# 801_USBHub-Framework.net
KiCad netlist of a schematic drawn in Altium Designer
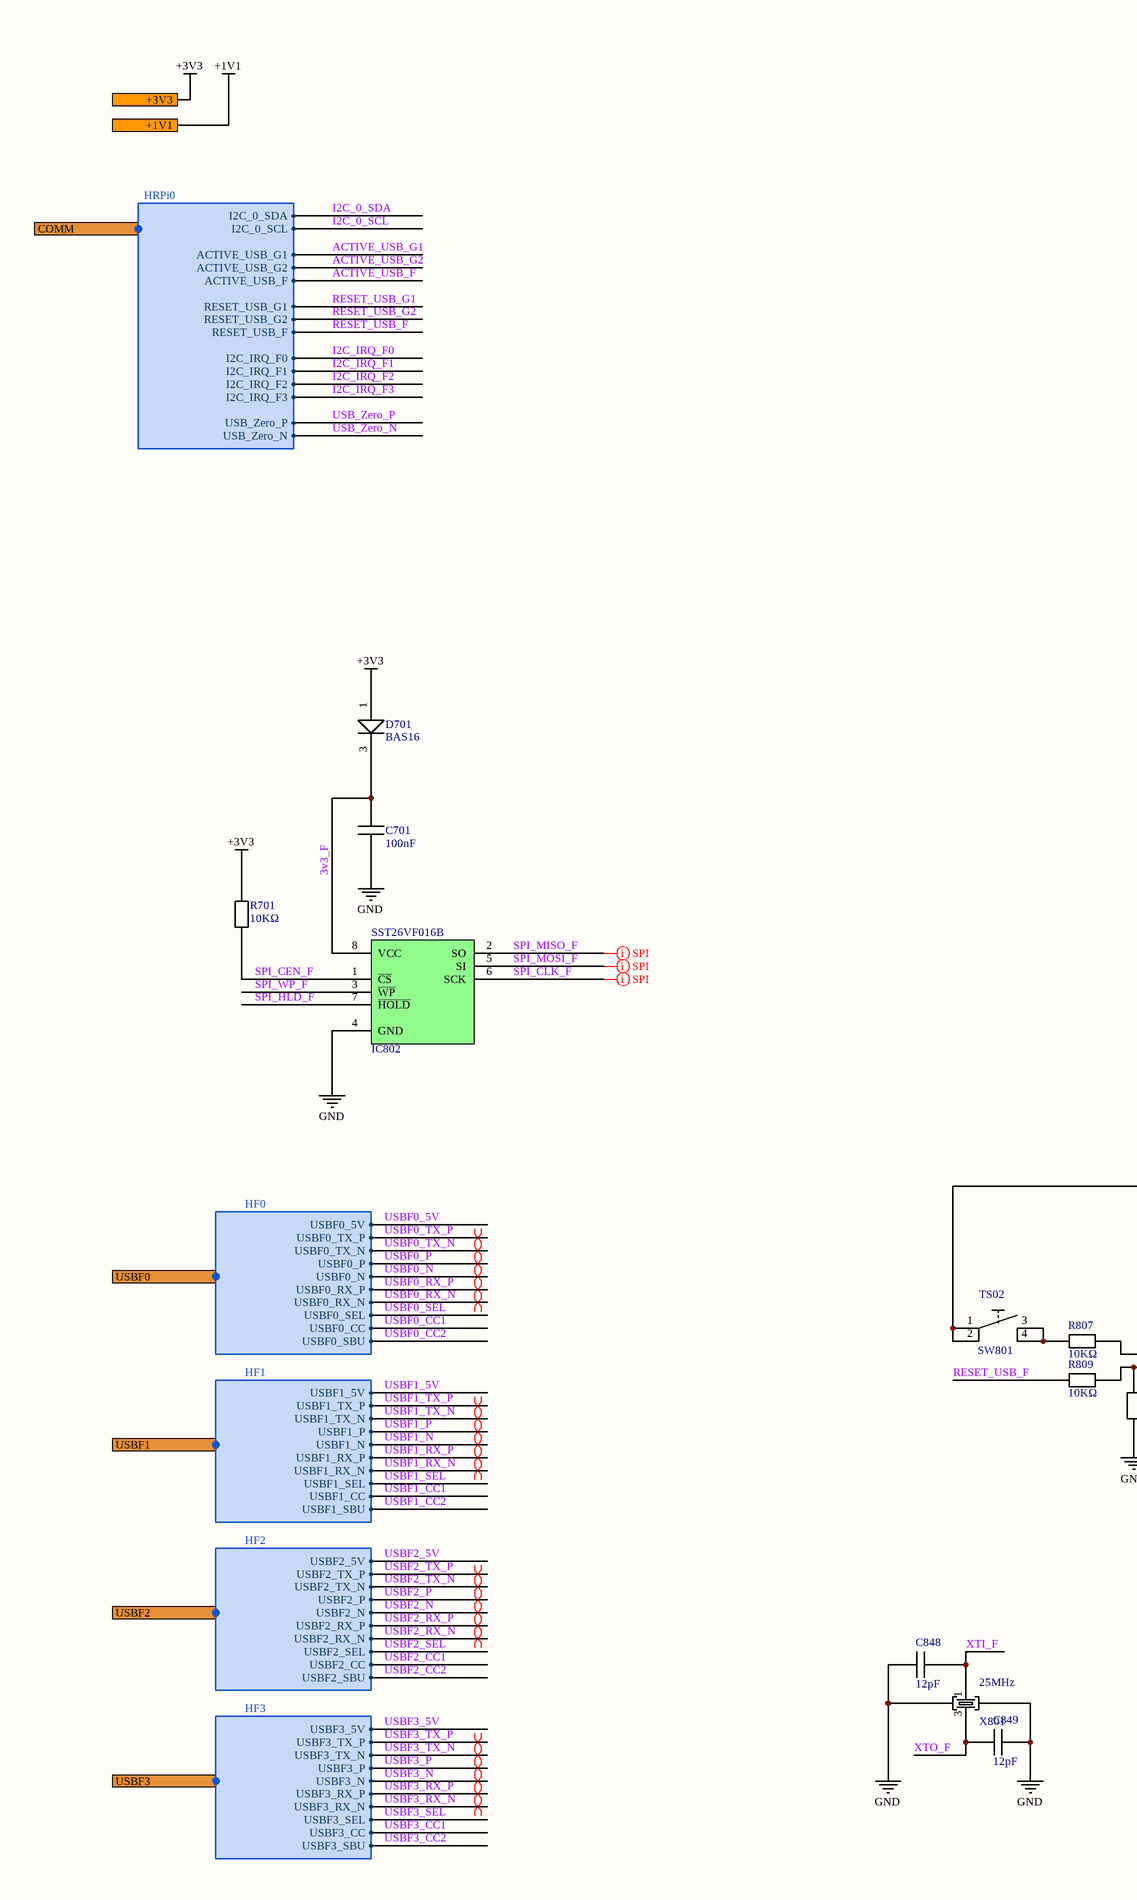
[diagram p0: 801_USBHub-Framework.SchDoc, left]
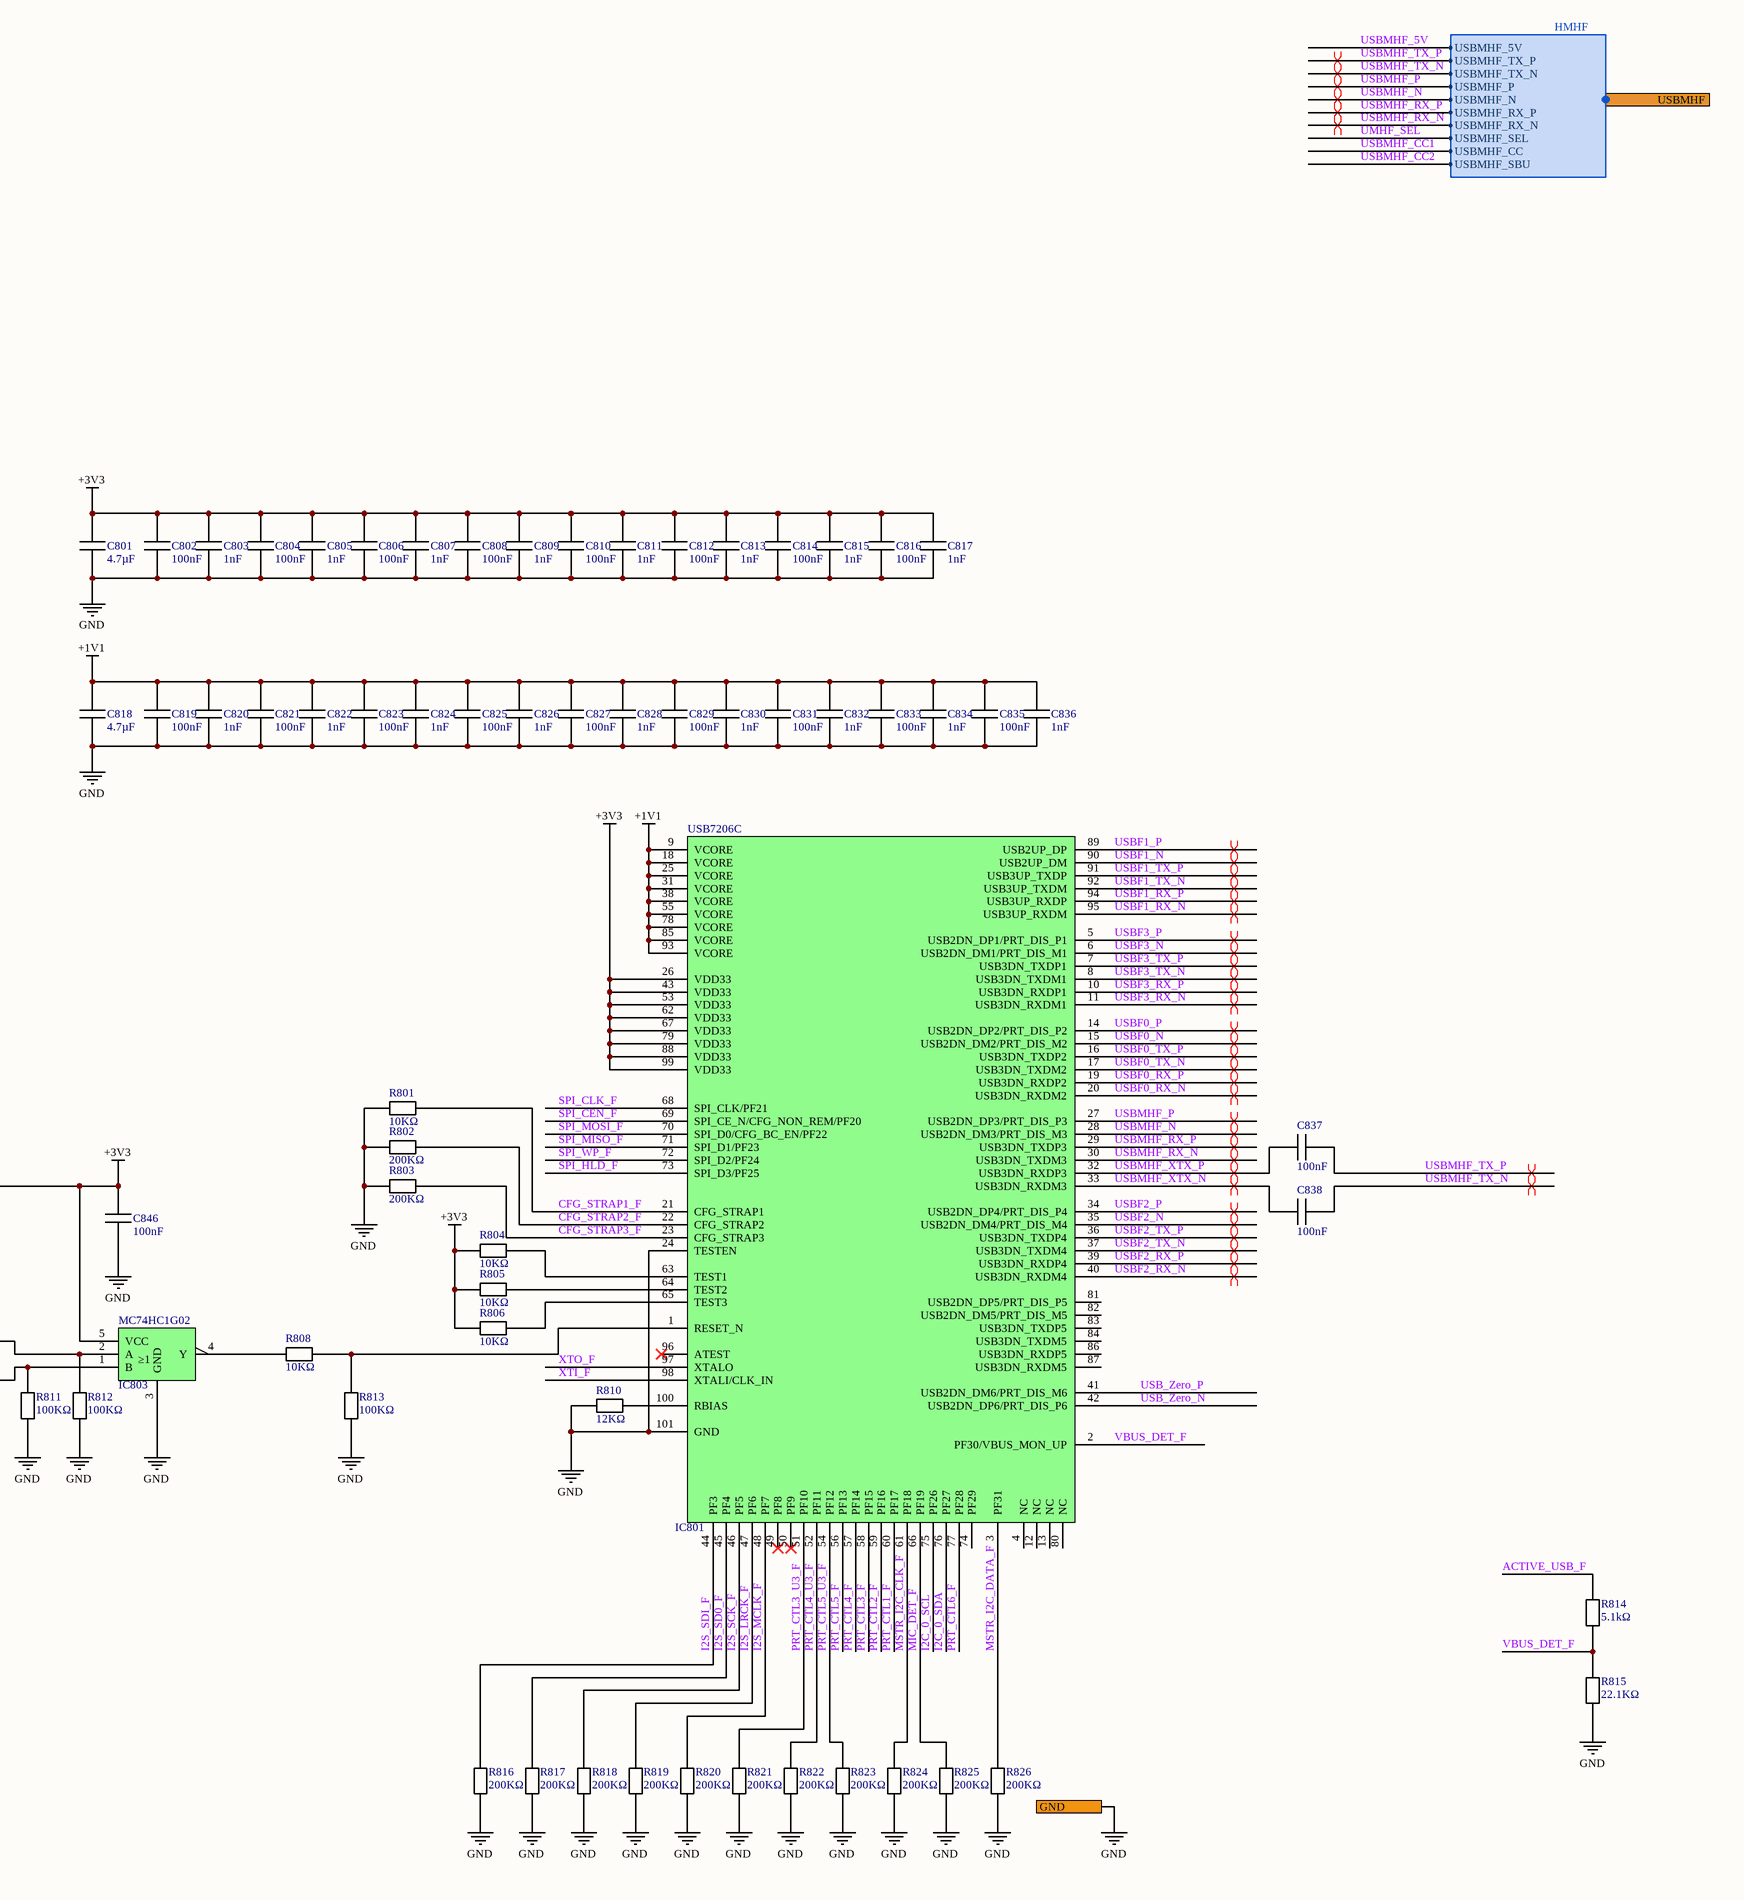
[diagram p1: 801_USBHub-Framework.SchDoc, right]

(export (version "E")
  (design (tool "Eeschema 10.0.6"))
  (components
    (comp (ref "C701")
      (value "100nF")
      (footprint "C0402")
      (description "100nF 16V 10% X7R")
      (fields
        (field (name "REFVAL") "100nF")
        (field (name "PART NUMBER") "CA0010")
        (field (name "MANFACTPART") "GCM155R71C104KA55D")
      )
      (libsource (lib "GTS_Database") (part "C"))
    )
    (comp (ref "C801")
      (value "4.7µF")
      (footprint "C0603")
      (description "4.7µF 16V 10% X5R")
      (fields
        (field (name "REFVAL") "4.7µF")
        (field (name "PART NUMBER") "CA0002")
        (field (name "MANFACTPART") "C1608X5R1C475K080AC")
      )
      (libsource (lib "GTS_Database") (part "C"))
    )
    (comp (ref "C802")
      (value "100nF")
      (footprint "C0402")
      (description "100nF 16V 10% X7R")
      (fields
        (field (name "REFVAL") "100nF")
        (field (name "PART NUMBER") "CA0010")
        (field (name "MANFACTPART") "GCM155R71C104KA55D")
      )
      (libsource (lib "GTS_Database") (part "C"))
    )
    (comp (ref "C803")
      (value "1nF")
      (footprint "C0402")
      (description "1nF 50V 1% C0G")
      (fields
        (field (name "REFVAL") "1nF")
        (field (name "PART NUMBER") "CA0031")
        (field (name "MANFACTPART") "GRT1555C1H102FA02D")
      )
      (libsource (lib "GTS_Database") (part "C"))
    )
    (comp (ref "C804")
      (value "100nF")
      (footprint "C0402")
      (description "100nF 16V 10% X7R")
      (fields
        (field (name "REFVAL") "100nF")
        (field (name "PART NUMBER") "CA0010")
        (field (name "MANFACTPART") "GCM155R71C104KA55D")
      )
      (libsource (lib "GTS_Database") (part "C"))
    )
    (comp (ref "C805")
      (value "1nF")
      (footprint "C0402")
      (description "1nF 50V 1% C0G")
      (fields
        (field (name "REFVAL") "1nF")
        (field (name "PART NUMBER") "CA0031")
        (field (name "MANFACTPART") "GRT1555C1H102FA02D")
      )
      (libsource (lib "GTS_Database") (part "C"))
    )
    (comp (ref "C806")
      (value "100nF")
      (footprint "C0402")
      (description "100nF 16V 10% X7R")
      (fields
        (field (name "REFVAL") "100nF")
        (field (name "PART NUMBER") "CA0010")
        (field (name "MANFACTPART") "GCM155R71C104KA55D")
      )
      (libsource (lib "GTS_Database") (part "C"))
    )
    (comp (ref "C807")
      (value "1nF")
      (footprint "C0402")
      (description "1nF 50V 1% C0G")
      (fields
        (field (name "REFVAL") "1nF")
        (field (name "PART NUMBER") "CA0031")
        (field (name "MANFACTPART") "GRT1555C1H102FA02D")
      )
      (libsource (lib "GTS_Database") (part "C"))
    )
    (comp (ref "C808")
      (value "100nF")
      (footprint "C0402")
      (description "100nF 16V 10% X7R")
      (fields
        (field (name "REFVAL") "100nF")
        (field (name "PART NUMBER") "CA0010")
        (field (name "MANFACTPART") "GCM155R71C104KA55D")
      )
      (libsource (lib "GTS_Database") (part "C"))
    )
    (comp (ref "C809")
      (value "1nF")
      (footprint "C0402")
      (description "1nF 50V 1% C0G")
      (fields
        (field (name "REFVAL") "1nF")
        (field (name "PART NUMBER") "CA0031")
        (field (name "MANFACTPART") "GRT1555C1H102FA02D")
      )
      (libsource (lib "GTS_Database") (part "C"))
    )
    (comp (ref "C810")
      (value "100nF")
      (footprint "C0402")
      (description "100nF 16V 10% X7R")
      (fields
        (field (name "REFVAL") "100nF")
        (field (name "PART NUMBER") "CA0010")
        (field (name "MANFACTPART") "GCM155R71C104KA55D")
      )
      (libsource (lib "GTS_Database") (part "C"))
    )
    (comp (ref "C811")
      (value "1nF")
      (footprint "C0402")
      (description "1nF 50V 1% C0G")
      (fields
        (field (name "REFVAL") "1nF")
        (field (name "PART NUMBER") "CA0031")
        (field (name "MANFACTPART") "GRT1555C1H102FA02D")
      )
      (libsource (lib "GTS_Database") (part "C"))
    )
    (comp (ref "C812")
      (value "100nF")
      (footprint "C0402")
      (description "100nF 16V 10% X7R")
      (fields
        (field (name "REFVAL") "100nF")
        (field (name "PART NUMBER") "CA0010")
        (field (name "MANFACTPART") "GCM155R71C104KA55D")
      )
      (libsource (lib "GTS_Database") (part "C"))
    )
    (comp (ref "C813")
      (value "1nF")
      (footprint "C0402")
      (description "1nF 50V 1% C0G")
      (fields
        (field (name "REFVAL") "1nF")
        (field (name "PART NUMBER") "CA0031")
        (field (name "MANFACTPART") "GRT1555C1H102FA02D")
      )
      (libsource (lib "GTS_Database") (part "C"))
    )
    (comp (ref "C814")
      (value "100nF")
      (footprint "C0402")
      (description "100nF 16V 10% X7R")
      (fields
        (field (name "REFVAL") "100nF")
        (field (name "PART NUMBER") "CA0010")
        (field (name "MANFACTPART") "GCM155R71C104KA55D")
      )
      (libsource (lib "GTS_Database") (part "C"))
    )
    (comp (ref "C815")
      (value "1nF")
      (footprint "C0402")
      (description "1nF 50V 1% C0G")
      (fields
        (field (name "REFVAL") "1nF")
        (field (name "PART NUMBER") "CA0031")
        (field (name "MANFACTPART") "GRT1555C1H102FA02D")
      )
      (libsource (lib "GTS_Database") (part "C"))
    )
    (comp (ref "C816")
      (value "100nF")
      (footprint "C0402")
      (description "100nF 16V 10% X7R")
      (fields
        (field (name "REFVAL") "100nF")
        (field (name "PART NUMBER") "CA0010")
        (field (name "MANFACTPART") "GCM155R71C104KA55D")
      )
      (libsource (lib "GTS_Database") (part "C"))
    )
    (comp (ref "C817")
      (value "1nF")
      (footprint "C0402")
      (description "1nF 50V 1% C0G")
      (fields
        (field (name "REFVAL") "1nF")
        (field (name "PART NUMBER") "CA0031")
        (field (name "MANFACTPART") "GRT1555C1H102FA02D")
      )
      (libsource (lib "GTS_Database") (part "C"))
    )
    (comp (ref "C818")
      (value "4.7µF")
      (footprint "C0603")
      (description "4.7µF 16V 10% X5R")
      (fields
        (field (name "REFVAL") "4.7µF")
        (field (name "PART NUMBER") "CA0002")
        (field (name "MANFACTPART") "C1608X5R1C475K080AC")
      )
      (libsource (lib "GTS_Database") (part "C"))
    )
    (comp (ref "C819")
      (value "100nF")
      (footprint "C0402")
      (description "100nF 16V 10% X7R")
      (fields
        (field (name "REFVAL") "100nF")
        (field (name "PART NUMBER") "CA0010")
        (field (name "MANFACTPART") "GCM155R71C104KA55D")
      )
      (libsource (lib "GTS_Database") (part "C"))
    )
    (comp (ref "C820")
      (value "1nF")
      (footprint "C0402")
      (description "1nF 50V 1% C0G")
      (fields
        (field (name "REFVAL") "1nF")
        (field (name "PART NUMBER") "CA0031")
        (field (name "MANFACTPART") "GRT1555C1H102FA02D")
      )
      (libsource (lib "GTS_Database") (part "C"))
    )
    (comp (ref "C821")
      (value "100nF")
      (footprint "C0402")
      (description "100nF 16V 10% X7R")
      (fields
        (field (name "REFVAL") "100nF")
        (field (name "PART NUMBER") "CA0010")
        (field (name "MANFACTPART") "GCM155R71C104KA55D")
      )
      (libsource (lib "GTS_Database") (part "C"))
    )
    (comp (ref "C822")
      (value "1nF")
      (footprint "C0402")
      (description "1nF 50V 1% C0G")
      (fields
        (field (name "REFVAL") "1nF")
        (field (name "PART NUMBER") "CA0031")
        (field (name "MANFACTPART") "GRT1555C1H102FA02D")
      )
      (libsource (lib "GTS_Database") (part "C"))
    )
    (comp (ref "C823")
      (value "100nF")
      (footprint "C0402")
      (description "100nF 16V 10% X7R")
      (fields
        (field (name "REFVAL") "100nF")
        (field (name "PART NUMBER") "CA0010")
        (field (name "MANFACTPART") "GCM155R71C104KA55D")
      )
      (libsource (lib "GTS_Database") (part "C"))
    )
    (comp (ref "C824")
      (value "1nF")
      (footprint "C0402")
      (description "1nF 50V 1% C0G")
      (fields
        (field (name "REFVAL") "1nF")
        (field (name "PART NUMBER") "CA0031")
        (field (name "MANFACTPART") "GRT1555C1H102FA02D")
      )
      (libsource (lib "GTS_Database") (part "C"))
    )
    (comp (ref "C825")
      (value "100nF")
      (footprint "C0402")
      (description "100nF 16V 10% X7R")
      (fields
        (field (name "REFVAL") "100nF")
        (field (name "PART NUMBER") "CA0010")
        (field (name "MANFACTPART") "GCM155R71C104KA55D")
      )
      (libsource (lib "GTS_Database") (part "C"))
    )
    (comp (ref "C826")
      (value "1nF")
      (footprint "C0402")
      (description "1nF 50V 1% C0G")
      (fields
        (field (name "REFVAL") "1nF")
        (field (name "PART NUMBER") "CA0031")
        (field (name "MANFACTPART") "GRT1555C1H102FA02D")
      )
      (libsource (lib "GTS_Database") (part "C"))
    )
    (comp (ref "C827")
      (value "100nF")
      (footprint "C0402")
      (description "100nF 16V 10% X7R")
      (fields
        (field (name "REFVAL") "100nF")
        (field (name "PART NUMBER") "CA0010")
        (field (name "MANFACTPART") "GCM155R71C104KA55D")
      )
      (libsource (lib "GTS_Database") (part "C"))
    )
    (comp (ref "C828")
      (value "1nF")
      (footprint "C0402")
      (description "1nF 50V 1% C0G")
      (fields
        (field (name "REFVAL") "1nF")
        (field (name "PART NUMBER") "CA0031")
        (field (name "MANFACTPART") "GRT1555C1H102FA02D")
      )
      (libsource (lib "GTS_Database") (part "C"))
    )
    (comp (ref "C829")
      (value "100nF")
      (footprint "C0402")
      (description "100nF 16V 10% X7R")
      (fields
        (field (name "REFVAL") "100nF")
        (field (name "PART NUMBER") "CA0010")
        (field (name "MANFACTPART") "GCM155R71C104KA55D")
      )
      (libsource (lib "GTS_Database") (part "C"))
    )
    (comp (ref "C830")
      (value "1nF")
      (footprint "C0402")
      (description "1nF 50V 1% C0G")
      (fields
        (field (name "REFVAL") "1nF")
        (field (name "PART NUMBER") "CA0031")
        (field (name "MANFACTPART") "GRT1555C1H102FA02D")
      )
      (libsource (lib "GTS_Database") (part "C"))
    )
    (comp (ref "C831")
      (value "100nF")
      (footprint "C0402")
      (description "100nF 16V 10% X7R")
      (fields
        (field (name "REFVAL") "100nF")
        (field (name "PART NUMBER") "CA0010")
        (field (name "MANFACTPART") "GCM155R71C104KA55D")
      )
      (libsource (lib "GTS_Database") (part "C"))
    )
    (comp (ref "C832")
      (value "1nF")
      (footprint "C0402")
      (description "1nF 50V 1% C0G")
      (fields
        (field (name "REFVAL") "1nF")
        (field (name "PART NUMBER") "CA0031")
        (field (name "MANFACTPART") "GRT1555C1H102FA02D")
      )
      (libsource (lib "GTS_Database") (part "C"))
    )
    (comp (ref "C833")
      (value "100nF")
      (footprint "C0402")
      (description "100nF 16V 10% X7R")
      (fields
        (field (name "REFVAL") "100nF")
        (field (name "PART NUMBER") "CA0010")
        (field (name "MANFACTPART") "GCM155R71C104KA55D")
      )
      (libsource (lib "GTS_Database") (part "C"))
    )
    (comp (ref "C834")
      (value "1nF")
      (footprint "C0402")
      (description "1nF 50V 1% C0G")
      (fields
        (field (name "REFVAL") "1nF")
        (field (name "PART NUMBER") "CA0031")
        (field (name "MANFACTPART") "GRT1555C1H102FA02D")
      )
      (libsource (lib "GTS_Database") (part "C"))
    )
    (comp (ref "C835")
      (value "100nF")
      (footprint "C0402")
      (description "100nF 16V 10% X7R")
      (fields
        (field (name "REFVAL") "100nF")
        (field (name "PART NUMBER") "CA0010")
        (field (name "MANFACTPART") "GCM155R71C104KA55D")
      )
      (libsource (lib "GTS_Database") (part "C"))
    )
    (comp (ref "C836")
      (value "1nF")
      (footprint "C0402")
      (description "1nF 50V 1% C0G")
      (fields
        (field (name "REFVAL") "1nF")
        (field (name "PART NUMBER") "CA0031")
        (field (name "MANFACTPART") "GRT1555C1H102FA02D")
      )
      (libsource (lib "GTS_Database") (part "C"))
    )
    (comp (ref "C837")
      (value "100nF")
      (footprint "C0402")
      (description "100nF 16V 10% X7R")
      (fields
        (field (name "REFVAL") "100nF")
        (field (name "PART NUMBER") "CA0010")
        (field (name "MANFACTPART") "GCM155R71C104KA55D")
      )
      (libsource (lib "GTS_Database") (part "C"))
    )
    (comp (ref "C838")
      (value "100nF")
      (footprint "C0402")
      (description "100nF 16V 10% X7R")
      (fields
        (field (name "REFVAL") "100nF")
        (field (name "PART NUMBER") "CA0010")
        (field (name "MANFACTPART") "GCM155R71C104KA55D")
      )
      (libsource (lib "GTS_Database") (part "C"))
    )
    (comp (ref "C846")
      (value "100nF")
      (footprint "C0402")
      (description "100nF 16V 10% X7R")
      (fields
        (field (name "REFVAL") "100nF")
        (field (name "PART NUMBER") "CA0010")
        (field (name "MANFACTPART") "GCM155R71C104KA55D")
      )
      (libsource (lib "GTS_Database") (part "C"))
    )
    (comp (ref "C848")
      (value "12pF")
      (footprint "C0402")
      (description "12pF 16V 1% C0G")
      (fields
        (field (name "REFVAL") "12pF")
        (field (name "PART NUMBER") "CA0059")
        (field (name "MANFACTPART") "VJ0402A120FXJCW1BC")
      )
      (libsource (lib "GTS_Database") (part "C"))
    )
    (comp (ref "C849")
      (value "12pF")
      (footprint "C0402")
      (description "12pF 16V 1% C0G")
      (fields
        (field (name "REFVAL") "12pF")
        (field (name "PART NUMBER") "CA0059")
        (field (name "MANFACTPART") "VJ0402A120FXJCW1BC")
      )
      (libsource (lib "GTS_Database") (part "C"))
    )
    (comp (ref "D701")
      (value "BAS16")
      (footprint "SOT-23")
      (description "Diodes - General Purpose, Power, Switching 100Vll Signal Switching Diodes 2A")
      (fields
        (field (name "REFVAL") "BAS16")
        (field (name "PART NUMBER") "DI0010")
        (field (name "MANFACTPART") "BAS16_R1_00001")
      )
      (libsource (lib "GTS_Database") (part "Ddefault_3P"))
    )
    (comp (ref "IC801")
      (value "USB7206C")
      (footprint "VQFN-100G_12X12")
      (description "6-Port USB 3.2 Gen 2 Controller Hub")
      (fields (field (name "REFVAL") "USB7206C") (field (name "PART NUMBER") "IC0065"))
      (libsource (lib "GTS_Database") (part "USB7206C"))
    )
    (comp (ref "IC802")
      (value "SST26VF016B")
      (footprint "SO-8")
      (description "16 Mbit Serial Quad I/O (SQI) Flash Memory")
      (fields
        (field (name "REFVAL") "SST26VF016B")
        (field (name "PART NUMBER") "IC0059")
        (field (name "MANFACTPART") "SST26VF016B-104I/SM")
      )
      (libsource (lib "GTS_Database") (part "SST26VF016B"))
    )
    (comp (ref "IC803")
      (value "MC74HC1G02")
      (footprint "TSOP-5")
      (description "Logic Gates 2-6V Single 2-Input NOR")
      (fields
        (field (name "REFVAL") "MC74HC1G02")
        (field (name "PART NUMBER") "IC0061")
        (field (name "MANFACTPART") "MC74HC1G02DTT1G")
      )
      (libsource (lib "GTS_Database") (part "MC74HC1G02"))
    )
    (comp (ref "R701")
      (value "10KΩ")
      (footprint "R0402")
      (description "10KΩ 1% 62.5mW")
      (fields
        (field (name "REFVAL") "10KΩ")
        (field (name "PART NUMBER") "RS0011")
        (field (name "MANFACTPART") "WR04X1002FTL")
      )
      (libsource (lib "GTS_Database") (part "R"))
    )
    (comp (ref "R801")
      (value "10KΩ")
      (footprint "R0402")
      (description "10KΩ 1% 62.5mW")
      (fields
        (field (name "REFVAL") "10KΩ")
        (field (name "PART NUMBER") "RS0011")
        (field (name "MANFACTPART") "WR04X1002FTL")
      )
      (libsource (lib "GTS_Database") (part "R"))
    )
    (comp (ref "R802")
      (value "200KΩ")
      (footprint "R0402")
      (description "200KΩ 1% 62.5mW 100PPM")
      (fields
        (field (name "REFVAL") "200KΩ")
        (field (name "PART NUMBER") "RS0045")
        (field (name "MANFACTPART") "CRG0402F200K")
      )
      (libsource (lib "GTS_Database") (part "R"))
    )
    (comp (ref "R803")
      (value "200KΩ")
      (footprint "R0402")
      (description "200KΩ 1% 62.5mW 100PPM")
      (fields
        (field (name "REFVAL") "200KΩ")
        (field (name "PART NUMBER") "RS0045")
        (field (name "MANFACTPART") "CRG0402F200K")
      )
      (libsource (lib "GTS_Database") (part "R"))
    )
    (comp (ref "R804")
      (value "10KΩ")
      (footprint "R0402")
      (description "10KΩ 1% 62.5mW")
      (fields
        (field (name "REFVAL") "10KΩ")
        (field (name "PART NUMBER") "RS0011")
        (field (name "MANFACTPART") "WR04X1002FTL")
      )
      (libsource (lib "GTS_Database") (part "R"))
    )
    (comp (ref "R805")
      (value "10KΩ")
      (footprint "R0402")
      (description "10KΩ 1% 62.5mW")
      (fields
        (field (name "REFVAL") "10KΩ")
        (field (name "PART NUMBER") "RS0011")
        (field (name "MANFACTPART") "WR04X1002FTL")
      )
      (libsource (lib "GTS_Database") (part "R"))
    )
    (comp (ref "R806")
      (value "10KΩ")
      (footprint "R0402")
      (description "10KΩ 1% 62.5mW")
      (fields
        (field (name "REFVAL") "10KΩ")
        (field (name "PART NUMBER") "RS0011")
        (field (name "MANFACTPART") "WR04X1002FTL")
      )
      (libsource (lib "GTS_Database") (part "R"))
    )
    (comp (ref "R807")
      (value "10KΩ")
      (footprint "R0402")
      (description "10KΩ 1% 62.5mW")
      (fields
        (field (name "REFVAL") "10KΩ")
        (field (name "PART NUMBER") "RS0011")
        (field (name "MANFACTPART") "WR04X1002FTL")
      )
      (libsource (lib "GTS_Database") (part "R"))
    )
    (comp (ref "R808")
      (value "10KΩ")
      (footprint "R0402")
      (description "10KΩ 1% 62.5mW")
      (fields
        (field (name "REFVAL") "10KΩ")
        (field (name "PART NUMBER") "RS0011")
        (field (name "MANFACTPART") "WR04X1002FTL")
      )
      (libsource (lib "GTS_Database") (part "R"))
    )
    (comp (ref "R809")
      (value "10KΩ")
      (footprint "R0402")
      (description "10KΩ 1% 62.5mW")
      (fields
        (field (name "REFVAL") "10KΩ")
        (field (name "PART NUMBER") "RS0011")
        (field (name "MANFACTPART") "WR04X1002FTL")
      )
      (libsource (lib "GTS_Database") (part "R"))
    )
    (comp (ref "R810")
      (value "12KΩ")
      (footprint "R0402")
      (description "12KΩ 1% 62.5mW")
      (fields
        (field (name "REFVAL") "12KΩ")
        (field (name "PART NUMBER") "RS0015")
        (field (name "MANFACTPART") "RC0402FR-1312KL")
      )
      (libsource (lib "GTS_Database") (part "R"))
    )
    (comp (ref "R811")
      (value "100KΩ")
      (footprint "R0402")
      (description "100KΩ 1% 62.5mW 100PPM")
      (fields
        (field (name "REFVAL") "100KΩ")
        (field (name "PART NUMBER") "RS0036")
        (field (name "MANFACTPART") "AC0402FR-13100KL")
      )
      (libsource (lib "GTS_Database") (part "R"))
    )
    (comp (ref "R812")
      (value "100KΩ")
      (footprint "R0402")
      (description "100KΩ 1% 62.5mW 100PPM")
      (fields
        (field (name "REFVAL") "100KΩ")
        (field (name "PART NUMBER") "RS0036")
        (field (name "MANFACTPART") "AC0402FR-13100KL")
      )
      (libsource (lib "GTS_Database") (part "R"))
    )
    (comp (ref "R813")
      (value "100KΩ")
      (footprint "R0402")
      (description "100KΩ 1% 62.5mW 100PPM")
      (fields
        (field (name "REFVAL") "100KΩ")
        (field (name "PART NUMBER") "RS0036")
        (field (name "MANFACTPART") "AC0402FR-13100KL")
      )
      (libsource (lib "GTS_Database") (part "R"))
    )
    (comp (ref "R814")
      (value "5.1kΩ")
      (footprint "R0402")
      (description "5.1KΩ 1% 62.5mW 100PPM")
      (fields
        (field (name "REFVAL") "5.1kΩ")
        (field (name "PART NUMBER") "RS0038")
        (field (name "MANFACTPART") "CRCW04025K10FKEDC")
      )
      (libsource (lib "GTS_Database") (part "R"))
    )
    (comp (ref "R815")
      (value "22.1KΩ")
      (footprint "R0603")
      (description "22.1KΩ 1% 100mW 100PPM")
      (fields
        (field (name "REFVAL") "22.1KΩ")
        (field (name "PART NUMBER") "RS0040")
        (field (name "MANFACTPART") "RC0603FR-0722K1L")
      )
      (libsource (lib "GTS_Database") (part "R"))
    )
    (comp (ref "R816")
      (value "200KΩ")
      (footprint "R0402")
      (description "200KΩ 1% 62.5mW 100PPM")
      (fields
        (field (name "REFVAL") "200KΩ")
        (field (name "PART NUMBER") "RS0045")
        (field (name "MANFACTPART") "CRG0402F200K")
      )
      (libsource (lib "GTS_Database") (part "R"))
    )
    (comp (ref "R817")
      (value "200KΩ")
      (footprint "R0402")
      (description "200KΩ 1% 62.5mW 100PPM")
      (fields
        (field (name "REFVAL") "200KΩ")
        (field (name "PART NUMBER") "RS0045")
        (field (name "MANFACTPART") "CRG0402F200K")
      )
      (libsource (lib "GTS_Database") (part "R"))
    )
    (comp (ref "R818")
      (value "200KΩ")
      (footprint "R0402")
      (description "200KΩ 1% 62.5mW 100PPM")
      (fields
        (field (name "REFVAL") "200KΩ")
        (field (name "PART NUMBER") "RS0045")
        (field (name "MANFACTPART") "CRG0402F200K")
      )
      (libsource (lib "GTS_Database") (part "R"))
    )
    (comp (ref "R819")
      (value "200KΩ")
      (footprint "R0402")
      (description "200KΩ 1% 62.5mW 100PPM")
      (fields
        (field (name "REFVAL") "200KΩ")
        (field (name "PART NUMBER") "RS0045")
        (field (name "MANFACTPART") "CRG0402F200K")
      )
      (libsource (lib "GTS_Database") (part "R"))
    )
    (comp (ref "R820")
      (value "200KΩ")
      (footprint "R0402")
      (description "200KΩ 1% 62.5mW 100PPM")
      (fields
        (field (name "REFVAL") "200KΩ")
        (field (name "PART NUMBER") "RS0045")
        (field (name "MANFACTPART") "CRG0402F200K")
      )
      (libsource (lib "GTS_Database") (part "R"))
    )
    (comp (ref "R821")
      (value "200KΩ")
      (footprint "R0402")
      (description "200KΩ 1% 62.5mW 100PPM")
      (fields
        (field (name "REFVAL") "200KΩ")
        (field (name "PART NUMBER") "RS0045")
        (field (name "MANFACTPART") "CRG0402F200K")
      )
      (libsource (lib "GTS_Database") (part "R"))
    )
    (comp (ref "R822")
      (value "200KΩ")
      (footprint "R0402")
      (description "200KΩ 1% 62.5mW 100PPM")
      (fields
        (field (name "REFVAL") "200KΩ")
        (field (name "PART NUMBER") "RS0045")
        (field (name "MANFACTPART") "CRG0402F200K")
      )
      (libsource (lib "GTS_Database") (part "R"))
    )
    (comp (ref "R823")
      (value "200KΩ")
      (footprint "R0402")
      (description "200KΩ 1% 62.5mW 100PPM")
      (fields
        (field (name "REFVAL") "200KΩ")
        (field (name "PART NUMBER") "RS0045")
        (field (name "MANFACTPART") "CRG0402F200K")
      )
      (libsource (lib "GTS_Database") (part "R"))
    )
    (comp (ref "R824")
      (value "200KΩ")
      (footprint "R0402")
      (description "200KΩ 1% 62.5mW 100PPM")
      (fields
        (field (name "REFVAL") "200KΩ")
        (field (name "PART NUMBER") "RS0045")
        (field (name "MANFACTPART") "CRG0402F200K")
      )
      (libsource (lib "GTS_Database") (part "R"))
    )
    (comp (ref "R825")
      (value "200KΩ")
      (footprint "R0402")
      (description "200KΩ 1% 62.5mW 100PPM")
      (fields
        (field (name "REFVAL") "200KΩ")
        (field (name "PART NUMBER") "RS0045")
        (field (name "MANFACTPART") "CRG0402F200K")
      )
      (libsource (lib "GTS_Database") (part "R"))
    )
    (comp (ref "R826")
      (value "200KΩ")
      (footprint "R0402")
      (description "200KΩ 1% 62.5mW 100PPM")
      (fields
        (field (name "REFVAL") "200KΩ")
        (field (name "PART NUMBER") "RS0045")
        (field (name "MANFACTPART") "CRG0402F200K")
      )
      (libsource (lib "GTS_Database") (part "R"))
    )
    (comp (ref "SW801")
      (value "TS02")
      (footprint "TS02")
      (description "TACTILE SWITCH SPST")
      (fields
        (field (name "REFVAL") "TS02")
        (field (name "PART NUMBER") "SW0005")
        (field (name "MANFACTPART") "TS02-66-50-BK-160-SCR-D")
      )
      (libsource (lib "GTS_Database") (part "SPST-2-4"))
    )
    (comp (ref "X801")
      (value "25MHz")
      (footprint "403W")
      (description "25MHz 8pF 20PPM")
      (fields
        (field (name "REFVAL") "25MHz")
        (field (name "PART NUMBER") "CR0003")
        (field (name "MANFACTPART") "403WF25012IK")
      )
      (libsource (lib "GTS_Database") (part "Crystal_1_3"))
    )
  )
  (nets
    (net (code "7") (name "+1V1") (class "Default")
      (node (ref "C818") (pin "1") (pinfunction "1_1") (pintype "passive"))
      (node (ref "C819") (pin "1") (pinfunction "1_1") (pintype "passive"))
      (node (ref "C820") (pin "1") (pinfunction "1_1") (pintype "passive"))
      (node (ref "C821") (pin "1") (pinfunction "1_1") (pintype "passive"))
      (node (ref "C822") (pin "1") (pinfunction "1_1") (pintype "passive"))
      (node (ref "C823") (pin "1") (pinfunction "1_1") (pintype "passive"))
      (node (ref "C824") (pin "1") (pinfunction "1_1") (pintype "passive"))
      (node (ref "C825") (pin "1") (pinfunction "1_1") (pintype "passive"))
      (node (ref "C826") (pin "1") (pinfunction "1_1") (pintype "passive"))
      (node (ref "C827") (pin "1") (pinfunction "1_1") (pintype "passive"))
      (node (ref "C828") (pin "1") (pinfunction "1_1") (pintype "passive"))
      (node (ref "C829") (pin "1") (pinfunction "1_1") (pintype "passive"))
      (node (ref "C830") (pin "1") (pinfunction "1_1") (pintype "passive"))
      (node (ref "C831") (pin "1") (pinfunction "1_1") (pintype "passive"))
      (node (ref "C832") (pin "1") (pinfunction "1_1") (pintype "passive"))
      (node (ref "C833") (pin "1") (pinfunction "1_1") (pintype "passive"))
      (node (ref "C834") (pin "1") (pinfunction "1_1") (pintype "passive"))
      (node (ref "C835") (pin "1") (pinfunction "1_1") (pintype "passive"))
      (node (ref "C836") (pin "1") (pinfunction "1_1") (pintype "passive"))
      (node (ref "IC801") (pin "18") (pinfunction "VCORE_18") (pintype "passive"))
      (node (ref "IC801") (pin "25") (pinfunction "VCORE_25") (pintype "passive"))
      (node (ref "IC801") (pin "31") (pinfunction "VCORE_31") (pintype "passive"))
      (node (ref "IC801") (pin "38") (pinfunction "VCORE_38") (pintype "passive"))
      (node (ref "IC801") (pin "55") (pinfunction "VCORE_55") (pintype "passive"))
      (node (ref "IC801") (pin "78") (pinfunction "VCORE_78") (pintype "passive"))
      (node (ref "IC801") (pin "85") (pinfunction "VCORE_85") (pintype "passive"))
      (node (ref "IC801") (pin "9") (pinfunction "VCORE_9") (pintype "passive"))
      (node (ref "IC801") (pin "93") (pinfunction "VCORE_93") (pintype "passive"))
    )
    (net (code "8") (name "+3V3") (class "Default")
      (node (ref "C801") (pin "1") (pinfunction "1_1") (pintype "passive"))
      (node (ref "C802") (pin "1") (pinfunction "1_1") (pintype "passive"))
      (node (ref "C803") (pin "1") (pinfunction "1_1") (pintype "passive"))
      (node (ref "C804") (pin "1") (pinfunction "1_1") (pintype "passive"))
      (node (ref "C805") (pin "1") (pinfunction "1_1") (pintype "passive"))
      (node (ref "C806") (pin "1") (pinfunction "1_1") (pintype "passive"))
      (node (ref "C807") (pin "1") (pinfunction "1_1") (pintype "passive"))
      (node (ref "C808") (pin "1") (pinfunction "1_1") (pintype "passive"))
      (node (ref "C809") (pin "1") (pinfunction "1_1") (pintype "passive"))
      (node (ref "C810") (pin "1") (pinfunction "1_1") (pintype "passive"))
      (node (ref "C811") (pin "1") (pinfunction "1_1") (pintype "passive"))
      (node (ref "C812") (pin "1") (pinfunction "1_1") (pintype "passive"))
      (node (ref "C813") (pin "1") (pinfunction "1_1") (pintype "passive"))
      (node (ref "C814") (pin "1") (pinfunction "1_1") (pintype "passive"))
      (node (ref "C815") (pin "1") (pinfunction "1_1") (pintype "passive"))
      (node (ref "C816") (pin "1") (pinfunction "1_1") (pintype "passive"))
      (node (ref "C817") (pin "1") (pinfunction "1_1") (pintype "passive"))
      (node (ref "C846") (pin "1") (pinfunction "1_1") (pintype "passive"))
      (node (ref "D701") (pin "1") (pinfunction "A_1") (pintype "passive"))
      (node (ref "IC801") (pin "26") (pinfunction "VDD33_26") (pintype "passive"))
      (node (ref "IC801") (pin "43") (pinfunction "VDD33_43") (pintype "passive"))
      (node (ref "IC801") (pin "53") (pinfunction "VDD33_53") (pintype "passive"))
      (node (ref "IC801") (pin "62") (pinfunction "VDD33_62") (pintype "passive"))
      (node (ref "IC801") (pin "67") (pinfunction "VDD33_67") (pintype "passive"))
      (node (ref "IC801") (pin "79") (pinfunction "VDD33_79") (pintype "passive"))
      (node (ref "IC801") (pin "88") (pinfunction "VDD33_88") (pintype "passive"))
      (node (ref "IC801") (pin "99") (pinfunction "VDD33_99") (pintype "passive"))
      (node (ref "IC803") (pin "5") (pinfunction "VCC_5") (pintype "passive"))
      (node (ref "R701") (pin "2") (pinfunction "2_2") (pintype "passive"))
      (node (ref "R804") (pin "1") (pinfunction "1_1") (pintype "passive"))
      (node (ref "R805") (pin "1") (pinfunction "1_1") (pintype "passive"))
      (node (ref "R806") (pin "1") (pinfunction "1_1") (pintype "passive"))
      (node (ref "SW801") (pin "1") (pinfunction "1_1") (pintype "passive"))
      (node (ref "SW801") (pin "2") (pinfunction "2_2") (pintype "passive"))
    )
    (net (code "9") (name "/3v3_F") (class "Default")
      (node (ref "C701") (pin "1") (pinfunction "1_1") (pintype "passive"))
      (node (ref "D701") (pin "3") (pinfunction "K_3") (pintype "passive"))
      (node (ref "IC802") (pin "8") (pinfunction "VCC_8") (pintype "passive"))
    )
    (net (code "10") (name "/ACTIVE_USB_F") (class "Default")
      (node (ref "R814") (pin "2") (pinfunction "2_2") (pintype "passive"))
    )
    (net (code "13") (name "/CFG_STRAP1_F") (class "Default")
      (node (ref "IC801") (pin "21") (pinfunction "CFG_STRAP1_21") (pintype "passive"))
      (node (ref "R801") (pin "1") (pinfunction "1_1") (pintype "passive"))
    )
    (net (code "14") (name "/CFG_STRAP2_F") (class "Default")
      (node (ref "IC801") (pin "22") (pinfunction "CFG_STRAP2_22") (pintype "passive"))
      (node (ref "R802") (pin "2") (pinfunction "2_2") (pintype "passive"))
    )
    (net (code "15") (name "/CFG_STRAP3_F") (class "Default")
      (node (ref "IC801") (pin "23") (pinfunction "CFG_STRAP3_23") (pintype "passive"))
      (node (ref "R803") (pin "2") (pinfunction "2_2") (pintype "passive"))
    )
    (net (code "16") (name "/I2C_0_SCL") (class "Default")
      (node (ref "IC801") (pin "75") (pinfunction "PF26_75") (pintype "passive"))
    )
    (net (code "17") (name "/I2C_0_SDA") (class "Default")
      (node (ref "IC801") (pin "76") (pinfunction "PF27_76") (pintype "passive"))
    )
    (net (code "22") (name "/I2S_LRCK_F") (class "Default")
      (node (ref "IC801") (pin "47") (pinfunction "PF6_47") (pintype "passive"))
      (node (ref "R819") (pin "2") (pinfunction "2_2") (pintype "passive"))
    )
    (net (code "23") (name "/I2S_MCLK_F") (class "Default")
      (node (ref "IC801") (pin "48") (pinfunction "PF7_48") (pintype "passive"))
      (node (ref "R820") (pin "2") (pinfunction "2_2") (pintype "passive"))
    )
    (net (code "24") (name "/I2S_SCK_F") (class "Default")
      (node (ref "IC801") (pin "46") (pinfunction "PF5_46") (pintype "passive"))
      (node (ref "R818") (pin "2") (pinfunction "2_2") (pintype "passive"))
    )
    (net (code "25") (name "/I2S_SD0_F") (class "Default")
      (node (ref "IC801") (pin "45") (pinfunction "PF4_45") (pintype "passive"))
      (node (ref "R817") (pin "2") (pinfunction "2_2") (pintype "passive"))
    )
    (net (code "26") (name "/I2S_SDI_F") (class "Default")
      (node (ref "IC801") (pin "44") (pinfunction "PF3_44") (pintype "passive"))
      (node (ref "R816") (pin "2") (pinfunction "2_2") (pintype "passive"))
    )
    (net (code "27") (name "/MIC_DET_F") (class "Default")
      (node (ref "IC801") (pin "66") (pinfunction "PF19_66") (pintype "passive"))
      (node (ref "R825") (pin "2") (pinfunction "2_2") (pintype "passive"))
    )
    (net (code "28") (name "/MSTR_I2C_CLK_F") (class "Default")
      (node (ref "IC801") (pin "61") (pinfunction "PF18_61") (pintype "passive"))
      (node (ref "R824") (pin "2") (pinfunction "2_2") (pintype "passive"))
    )
    (net (code "29") (name "/MSTR_I2C_DATA_F") (class "Default")
      (node (ref "IC801") (pin "3") (pinfunction "PF31_3") (pintype "passive"))
      (node (ref "R826") (pin "2") (pinfunction "2_2") (pintype "passive"))
    )
    (net (code "30") (name "/PRT_CTL1_F") (class "Default")
      (node (ref "IC801") (pin "60") (pinfunction "PF17_60") (pintype "passive"))
    )
    (net (code "31") (name "/PRT_CTL2_F") (class "Default")
      (node (ref "IC801") (pin "59") (pinfunction "PF16_59") (pintype "passive"))
    )
    (net (code "32") (name "/PRT_CTL3_F") (class "Default")
      (node (ref "IC801") (pin "58") (pinfunction "PF15_58") (pintype "passive"))
    )
    (net (code "33") (name "/PRT_CTL3_U3_F") (class "Default")
      (node (ref "IC801") (pin "51") (pinfunction "PF10_51") (pintype "passive"))
      (node (ref "R821") (pin "2") (pinfunction "2_2") (pintype "passive"))
    )
    (net (code "34") (name "/PRT_CTL4_F") (class "Default")
      (node (ref "IC801") (pin "57") (pinfunction "PF14_57") (pintype "passive"))
    )
    (net (code "35") (name "/PRT_CTL4_U3_F") (class "Default")
      (node (ref "IC801") (pin "52") (pinfunction "PF11_52") (pintype "passive"))
      (node (ref "R822") (pin "2") (pinfunction "2_2") (pintype "passive"))
    )
    (net (code "36") (name "/PRT_CTL5_F") (class "Default")
      (node (ref "IC801") (pin "56") (pinfunction "PF13_56") (pintype "passive"))
    )
    (net (code "37") (name "/PRT_CTL5_U3_F") (class "Default")
      (node (ref "IC801") (pin "54") (pinfunction "PF12_54") (pintype "passive"))
      (node (ref "R823") (pin "2") (pinfunction "2_2") (pintype "passive"))
    )
    (net (code "38") (name "/PRT_CTL6_F") (class "Default")
      (node (ref "IC801") (pin "77") (pinfunction "PF28_77") (pintype "passive"))
    )
    (net (code "39") (name "/RESET_USB_F") (class "Default")
      (node (ref "R809") (pin "2") (pinfunction "2_2") (pintype "passive"))
    )
    (net (code "42") (name "/SPI_CEN_F") (class "Default")
      (node (ref "IC801") (pin "69") (pinfunction "SPI_CE_N/CFG_NON_REM/PF20_69") (pintype "passive"))
      (node (ref "IC802") (pin "1") (pinfunction "CS_1") (pintype "passive"))
      (node (ref "R701") (pin "1") (pinfunction "1_1") (pintype "passive"))
    )
    (net (code "43") (name "/SPI_CLK_F") (class "Default")
      (node (ref "IC801") (pin "68") (pinfunction "SPI_CLK/PF21_68") (pintype "passive"))
      (node (ref "IC802") (pin "6") (pinfunction "SCK_6") (pintype "passive"))
    )
    (net (code "44") (name "/SPI_HLD_F") (class "Default")
      (node (ref "IC801") (pin "73") (pinfunction "SPI_D3/PF25_73") (pintype "passive"))
      (node (ref "IC802") (pin "7") (pinfunction "HOLD_7") (pintype "passive"))
    )
    (net (code "45") (name "/SPI_MISO_F") (class "Default")
      (node (ref "IC801") (pin "71") (pinfunction "SPI_D1/PF23_71") (pintype "passive"))
      (node (ref "IC802") (pin "2") (pinfunction "SO_2") (pintype "passive"))
    )
    (net (code "46") (name "/SPI_MOSI_F") (class "Default")
      (node (ref "IC801") (pin "70") (pinfunction "SPI_D0/CFG_BC_EN/PF22_70") (pintype "passive"))
      (node (ref "IC802") (pin "5") (pinfunction "SI_5") (pintype "passive"))
    )
    (net (code "47") (name "/SPI_WP_F") (class "Default")
      (node (ref "IC801") (pin "72") (pinfunction "SPI_D2/PF24_72") (pintype "passive"))
      (node (ref "IC802") (pin "3") (pinfunction "WP_3") (pintype "passive"))
    )
    (net (code "52") (name "/USBF0_N") (class "Default")
      (node (ref "IC801") (pin "15") (pinfunction "USB2DN_DM2/PRT_DIS_M2_15") (pintype "passive"))
    )
    (net (code "53") (name "/USBF0_P") (class "Default")
      (node (ref "IC801") (pin "14") (pinfunction "USB2DN_DP2/PRT_DIS_P2_14") (pintype "passive"))
    )
    (net (code "54") (name "/USBF0_RX_N") (class "Default")
      (node (ref "IC801") (pin "20") (pinfunction "USB3DN_RXDM2_20") (pintype "passive"))
    )
    (net (code "55") (name "/USBF0_RX_P") (class "Default")
      (node (ref "IC801") (pin "19") (pinfunction "USB3DN_RXDP2_19") (pintype "passive"))
    )
    (net (code "57") (name "/USBF0_TX_N") (class "Default")
      (node (ref "IC801") (pin "17") (pinfunction "USB3DN_TXDM2_17") (pintype "passive"))
    )
    (net (code "58") (name "/USBF0_TX_P") (class "Default")
      (node (ref "IC801") (pin "16") (pinfunction "USB3DN_TXDP2_16") (pintype "passive"))
    )
    (net (code "62") (name "/USBF1_N") (class "Default")
      (node (ref "IC801") (pin "90") (pinfunction "USB2UP_DM_90") (pintype "passive"))
    )
    (net (code "63") (name "/USBF1_P") (class "Default")
      (node (ref "IC801") (pin "89") (pinfunction "USB2UP_DP_89") (pintype "passive"))
    )
    (net (code "64") (name "/USBF1_RX_N") (class "Default")
      (node (ref "IC801") (pin "95") (pinfunction "USB3UP_RXDM_95") (pintype "passive"))
    )
    (net (code "65") (name "/USBF1_RX_P") (class "Default")
      (node (ref "IC801") (pin "94") (pinfunction "USB3UP_RXDP_94") (pintype "passive"))
    )
    (net (code "67") (name "/USBF1_TX_N") (class "Default")
      (node (ref "IC801") (pin "92") (pinfunction "USB3UP_TXDM_92") (pintype "passive"))
    )
    (net (code "68") (name "/USBF1_TX_P") (class "Default")
      (node (ref "IC801") (pin "91") (pinfunction "USB3UP_TXDP_91") (pintype "passive"))
    )
    (net (code "72") (name "/USBF2_N") (class "Default")
      (node (ref "IC801") (pin "35") (pinfunction "USB2DN_DM4/PRT_DIS_M4_35") (pintype "passive"))
    )
    (net (code "73") (name "/USBF2_P") (class "Default")
      (node (ref "IC801") (pin "34") (pinfunction "USB2DN_DP4/PRT_DIS_P4_34") (pintype "passive"))
    )
    (net (code "74") (name "/USBF2_RX_N") (class "Default")
      (node (ref "IC801") (pin "40") (pinfunction "USB3DN_RXDM4_40") (pintype "passive"))
    )
    (net (code "75") (name "/USBF2_RX_P") (class "Default")
      (node (ref "IC801") (pin "39") (pinfunction "USB3DN_RXDP4_39") (pintype "passive"))
    )
    (net (code "77") (name "/USBF2_TX_N") (class "Default")
      (node (ref "IC801") (pin "37") (pinfunction "USB3DN_TXDM4_37") (pintype "passive"))
    )
    (net (code "78") (name "/USBF2_TX_P") (class "Default")
      (node (ref "IC801") (pin "36") (pinfunction "USB3DN_TXDP4_36") (pintype "passive"))
    )
    (net (code "82") (name "/USBF3_N") (class "Default")
      (node (ref "IC801") (pin "6") (pinfunction "USB2DN_DM1/PRT_DIS_M1_6") (pintype "passive"))
    )
    (net (code "83") (name "/USBF3_P") (class "Default")
      (node (ref "IC801") (pin "5") (pinfunction "USB2DN_DP1/PRT_DIS_P1_5") (pintype "passive"))
    )
    (net (code "84") (name "/USBF3_RX_N") (class "Default")
      (node (ref "IC801") (pin "11") (pinfunction "USB3DN_RXDM1_11") (pintype "passive"))
    )
    (net (code "85") (name "/USBF3_RX_P") (class "Default")
      (node (ref "IC801") (pin "10") (pinfunction "USB3DN_RXDP1_10") (pintype "passive"))
    )
    (net (code "87") (name "/USBF3_TX_N") (class "Default")
      (node (ref "IC801") (pin "8") (pinfunction "USB3DN_TXDM1_8") (pintype "passive"))
    )
    (net (code "88") (name "/USBF3_TX_P") (class "Default")
      (node (ref "IC801") (pin "7") (pinfunction "USB3DN_TXDP1_7") (pintype "passive"))
    )
    (net (code "92") (name "/USBMHF_N") (class "Default")
      (node (ref "IC801") (pin "28") (pinfunction "USB2DN_DM3/PRT_DIS_M3_28") (pintype "passive"))
    )
    (net (code "93") (name "/USBMHF_P") (class "Default")
      (node (ref "IC801") (pin "27") (pinfunction "USB2DN_DP3/PRT_DIS_P3_27") (pintype "passive"))
    )
    (net (code "94") (name "/USBMHF_RX_N") (class "Default")
      (node (ref "IC801") (pin "30") (pinfunction "USB3DN_TXDM3_30") (pintype "passive"))
    )
    (net (code "95") (name "/USBMHF_RX_P") (class "Default")
      (node (ref "IC801") (pin "29") (pinfunction "USB3DN_TXDP3_29") (pintype "passive"))
    )
    (net (code "96") (name "/USBMHF_TX_N") (class "Default")
      (node (ref "C838") (pin "2") (pinfunction "2_2") (pintype "passive"))
    )
    (net (code "97") (name "/USBMHF_TX_P") (class "Default")
      (node (ref "C837") (pin "2") (pinfunction "2_2") (pintype "passive"))
    )
    (net (code "98") (name "/USBMHF_XTX_N") (class "Default")
      (node (ref "C838") (pin "1") (pinfunction "1_1") (pintype "passive"))
      (node (ref "IC801") (pin "33") (pinfunction "USB3DN_RXDM3_33") (pintype "passive"))
    )
    (net (code "99") (name "/USBMHF_XTX_P") (class "Default")
      (node (ref "C837") (pin "1") (pinfunction "1_1") (pintype "passive"))
      (node (ref "IC801") (pin "32") (pinfunction "USB3DN_RXDP3_32") (pintype "passive"))
    )
    (net (code "100") (name "/USB_Zero_N") (class "Default")
      (node (ref "IC801") (pin "42") (pinfunction "USB2DN_DP6/PRT_DIS_P6_42") (pintype "passive"))
    )
    (net (code "101") (name "/USB_Zero_P") (class "Default")
      (node (ref "IC801") (pin "41") (pinfunction "USB2DN_DM6/PRT_DIS_M6_41") (pintype "passive"))
    )
    (net (code "102") (name "/VBUS_DET_F") (class "Default")
      (node (ref "IC801") (pin "2") (pinfunction "PF30/VBUS_MON_UP_2") (pintype "passive"))
      (node (ref "R814") (pin "1") (pinfunction "1_1") (pintype "passive"))
      (node (ref "R815") (pin "2") (pinfunction "2_2") (pintype "passive"))
    )
    (net (code "103") (name "/XTI_F") (class "Default")
      (node (ref "C848") (pin "2") (pinfunction "2_2") (pintype "passive"))
      (node (ref "IC801") (pin "98") (pinfunction "XTALI/CLK_IN_98") (pintype "passive"))
      (node (ref "X801") (pin "1") (pinfunction "1_1") (pintype "passive"))
    )
    (net (code "104") (name "/XTO_F") (class "Default")
      (node (ref "C849") (pin "1") (pinfunction "1_1") (pintype "passive"))
      (node (ref "IC801") (pin "97") (pinfunction "XTALO_97") (pintype "passive"))
      (node (ref "X801") (pin "3") (pinfunction "3_3") (pintype "passive"))
    )
    (net (code "111") (name "GND") (class "Default")
      (node (ref "C701") (pin "2") (pinfunction "2_2") (pintype "passive"))
      (node (ref "C801") (pin "2") (pinfunction "2_2") (pintype "passive"))
      (node (ref "C802") (pin "2") (pinfunction "2_2") (pintype "passive"))
      (node (ref "C803") (pin "2") (pinfunction "2_2") (pintype "passive"))
      (node (ref "C804") (pin "2") (pinfunction "2_2") (pintype "passive"))
      (node (ref "C805") (pin "2") (pinfunction "2_2") (pintype "passive"))
      (node (ref "C806") (pin "2") (pinfunction "2_2") (pintype "passive"))
      (node (ref "C807") (pin "2") (pinfunction "2_2") (pintype "passive"))
      (node (ref "C808") (pin "2") (pinfunction "2_2") (pintype "passive"))
      (node (ref "C809") (pin "2") (pinfunction "2_2") (pintype "passive"))
      (node (ref "C810") (pin "2") (pinfunction "2_2") (pintype "passive"))
      (node (ref "C811") (pin "2") (pinfunction "2_2") (pintype "passive"))
      (node (ref "C812") (pin "2") (pinfunction "2_2") (pintype "passive"))
      (node (ref "C813") (pin "2") (pinfunction "2_2") (pintype "passive"))
      (node (ref "C814") (pin "2") (pinfunction "2_2") (pintype "passive"))
      (node (ref "C815") (pin "2") (pinfunction "2_2") (pintype "passive"))
      (node (ref "C816") (pin "2") (pinfunction "2_2") (pintype "passive"))
      (node (ref "C817") (pin "2") (pinfunction "2_2") (pintype "passive"))
      (node (ref "C818") (pin "2") (pinfunction "2_2") (pintype "passive"))
      (node (ref "C819") (pin "2") (pinfunction "2_2") (pintype "passive"))
      (node (ref "C820") (pin "2") (pinfunction "2_2") (pintype "passive"))
      (node (ref "C821") (pin "2") (pinfunction "2_2") (pintype "passive"))
      (node (ref "C822") (pin "2") (pinfunction "2_2") (pintype "passive"))
      (node (ref "C823") (pin "2") (pinfunction "2_2") (pintype "passive"))
      (node (ref "C824") (pin "2") (pinfunction "2_2") (pintype "passive"))
      (node (ref "C825") (pin "2") (pinfunction "2_2") (pintype "passive"))
      (node (ref "C826") (pin "2") (pinfunction "2_2") (pintype "passive"))
      (node (ref "C827") (pin "2") (pinfunction "2_2") (pintype "passive"))
      (node (ref "C828") (pin "2") (pinfunction "2_2") (pintype "passive"))
      (node (ref "C829") (pin "2") (pinfunction "2_2") (pintype "passive"))
      (node (ref "C830") (pin "2") (pinfunction "2_2") (pintype "passive"))
      (node (ref "C831") (pin "2") (pinfunction "2_2") (pintype "passive"))
      (node (ref "C832") (pin "2") (pinfunction "2_2") (pintype "passive"))
      (node (ref "C833") (pin "2") (pinfunction "2_2") (pintype "passive"))
      (node (ref "C834") (pin "2") (pinfunction "2_2") (pintype "passive"))
      (node (ref "C835") (pin "2") (pinfunction "2_2") (pintype "passive"))
      (node (ref "C836") (pin "2") (pinfunction "2_2") (pintype "passive"))
      (node (ref "C846") (pin "2") (pinfunction "2_2") (pintype "passive"))
      (node (ref "C848") (pin "1") (pinfunction "1_1") (pintype "passive"))
      (node (ref "C849") (pin "2") (pinfunction "2_2") (pintype "passive"))
      (node (ref "IC801") (pin "101") (pinfunction "GND_101") (pintype "passive"))
      (node (ref "IC801") (pin "24") (pinfunction "TESTEN_24") (pintype "passive"))
      (node (ref "IC802") (pin "4") (pinfunction "GND_4") (pintype "passive"))
      (node (ref "IC803") (pin "3") (pinfunction "GND_3") (pintype "passive"))
      (node (ref "R801") (pin "2") (pinfunction "2_2") (pintype "passive"))
      (node (ref "R802") (pin "1") (pinfunction "1_1") (pintype "passive"))
      (node (ref "R803") (pin "1") (pinfunction "1_1") (pintype "passive"))
      (node (ref "R810") (pin "1") (pinfunction "1_1") (pintype "passive"))
      (node (ref "R811") (pin "1") (pinfunction "1_1") (pintype "passive"))
      (node (ref "R812") (pin "1") (pinfunction "1_1") (pintype "passive"))
      (node (ref "R813") (pin "1") (pinfunction "1_1") (pintype "passive"))
      (node (ref "R815") (pin "1") (pinfunction "1_1") (pintype "passive"))
      (node (ref "R816") (pin "1") (pinfunction "1_1") (pintype "passive"))
      (node (ref "R817") (pin "1") (pinfunction "1_1") (pintype "passive"))
      (node (ref "R818") (pin "1") (pinfunction "1_1") (pintype "passive"))
      (node (ref "R819") (pin "1") (pinfunction "1_1") (pintype "passive"))
      (node (ref "R820") (pin "1") (pinfunction "1_1") (pintype "passive"))
      (node (ref "R821") (pin "1") (pinfunction "1_1") (pintype "passive"))
      (node (ref "R822") (pin "1") (pinfunction "1_1") (pintype "passive"))
      (node (ref "R823") (pin "1") (pinfunction "1_1") (pintype "passive"))
      (node (ref "R824") (pin "1") (pinfunction "1_1") (pintype "passive"))
      (node (ref "R825") (pin "1") (pinfunction "1_1") (pintype "passive"))
      (node (ref "R826") (pin "1") (pinfunction "1_1") (pintype "passive"))
      (node (ref "X801") (pin "2") (pinfunction "2_2") (pintype "passive"))
      (node (ref "X801") (pin "4") (pinfunction "4_4") (pintype "passive"))
    )
    (net (code "112") (name "Net-(IC801-RBIAS)") (class "Default")
      (node (ref "IC801") (pin "100") (pinfunction "RBIAS_100") (pintype "passive"))
      (node (ref "R810") (pin "2") (pinfunction "2_2") (pintype "passive"))
    )
    (net (code "113") (name "Net-(IC801-RESET_N)") (class "Default")
      (node (ref "IC801") (pin "1") (pinfunction "RESET_N_1") (pintype "passive"))
      (node (ref "R808") (pin "2") (pinfunction "2_2") (pintype "passive"))
      (node (ref "R813") (pin "2") (pinfunction "2_2") (pintype "passive"))
    )
    (net (code "114") (name "Net-(IC801-TEST1)") (class "Default")
      (node (ref "IC801") (pin "63") (pinfunction "TEST1_63") (pintype "passive"))
      (node (ref "R804") (pin "2") (pinfunction "2_2") (pintype "passive"))
    )
    (net (code "115") (name "Net-(IC801-TEST2)") (class "Default")
      (node (ref "IC801") (pin "64") (pinfunction "TEST2_64") (pintype "passive"))
      (node (ref "R805") (pin "2") (pinfunction "2_2") (pintype "passive"))
    )
    (net (code "116") (name "Net-(IC801-TEST3)") (class "Default")
      (node (ref "IC801") (pin "65") (pinfunction "TEST3_65") (pintype "passive"))
      (node (ref "R806") (pin "2") (pinfunction "2_2") (pintype "passive"))
    )
    (net (code "117") (name "Net-(IC803-A)") (class "Default")
      (node (ref "IC803") (pin "2") (pinfunction "A_2") (pintype "passive"))
      (node (ref "R807") (pin "1") (pinfunction "1_1") (pintype "passive"))
      (node (ref "R812") (pin "2") (pinfunction "2_2") (pintype "passive"))
    )
    (net (code "118") (name "Net-(IC803-B)") (class "Default")
      (node (ref "IC803") (pin "1") (pinfunction "B_1") (pintype "passive"))
      (node (ref "R809") (pin "1") (pinfunction "1_1") (pintype "passive"))
      (node (ref "R811") (pin "2") (pinfunction "2_2") (pintype "passive"))
    )
    (net (code "119") (name "Net-(IC803-Y)") (class "Default")
      (node (ref "IC803") (pin "4") (pinfunction "Y_4") (pintype "passive"))
      (node (ref "R808") (pin "1") (pinfunction "1_1") (pintype "passive"))
    )
    (net (code "120") (name "Net-(R807-Pad2)") (class "Default")
      (node (ref "R807") (pin "2") (pinfunction "2_2") (pintype "passive"))
      (node (ref "SW801") (pin "3") (pinfunction "3_3") (pintype "passive"))
      (node (ref "SW801") (pin "4") (pinfunction "4_4") (pintype "passive"))
    )
    (net (code "121") (name "unconnected-(IC801-ATEST-Pad96)") (class "Default")
      (node (ref "IC801") (pin "96") (pinfunction "ATEST_96") (pintype "passive+no_connect"))
    )
    (net (code "122") (name "unconnected-(IC801-NC-Pad4)") (class "Default")
      (node (ref "IC801") (pin "4") (pinfunction "NC_4") (pintype "passive"))
    )
    (net (code "123") (name "unconnected-(IC801-NC-Pad12)") (class "Default")
      (node (ref "IC801") (pin "12") (pinfunction "NC_12") (pintype "passive"))
    )
    (net (code "124") (name "unconnected-(IC801-NC-Pad13)") (class "Default")
      (node (ref "IC801") (pin "13") (pinfunction "NC_13") (pintype "passive"))
    )
    (net (code "125") (name "unconnected-(IC801-NC-Pad80)") (class "Default")
      (node (ref "IC801") (pin "80") (pinfunction "NC_80") (pintype "passive"))
    )
    (net (code "126") (name "unconnected-(IC801-PF8-Pad49)") (class "Default")
      (node (ref "IC801") (pin "49") (pinfunction "PF8_49") (pintype "passive+no_connect"))
    )
    (net (code "127") (name "unconnected-(IC801-PF9-Pad50)") (class "Default")
      (node (ref "IC801") (pin "50") (pinfunction "PF9_50") (pintype "passive+no_connect"))
    )
    (net (code "128") (name "unconnected-(IC801-PF29-Pad74)") (class "Default")
      (node (ref "IC801") (pin "74") (pinfunction "PF29_74") (pintype "passive"))
    )
    (net (code "129") (name "unconnected-(IC801-USB2DN_DM5{slash}PRT_DIS_M5-Pad82)") (class "Default")
      (node (ref "IC801") (pin "82") (pinfunction "USB2DN_DM5/PRT_DIS_M5_82") (pintype "passive"))
    )
    (net (code "130") (name "unconnected-(IC801-USB2DN_DP5{slash}PRT_DIS_P5-Pad81)") (class "Default")
      (node (ref "IC801") (pin "81") (pinfunction "USB2DN_DP5/PRT_DIS_P5_81") (pintype "passive"))
    )
    (net (code "131") (name "unconnected-(IC801-USB3DN_RXDM5-Pad87)") (class "Default")
      (node (ref "IC801") (pin "87") (pinfunction "USB3DN_RXDM5_87") (pintype "passive"))
    )
    (net (code "132") (name "unconnected-(IC801-USB3DN_RXDP5-Pad86)") (class "Default")
      (node (ref "IC801") (pin "86") (pinfunction "USB3DN_RXDP5_86") (pintype "passive"))
    )
    (net (code "133") (name "unconnected-(IC801-USB3DN_TXDM5-Pad84)") (class "Default")
      (node (ref "IC801") (pin "84") (pinfunction "USB3DN_TXDM5_84") (pintype "passive"))
    )
    (net (code "134") (name "unconnected-(IC801-USB3DN_TXDP5-Pad83)") (class "Default")
      (node (ref "IC801") (pin "83") (pinfunction "USB3DN_TXDP5_83") (pintype "passive"))
    )
  )
)
